# HLK_RM60_KIT_V1_1.net
KiCad netlist of a schematic drawn in Altium Designer
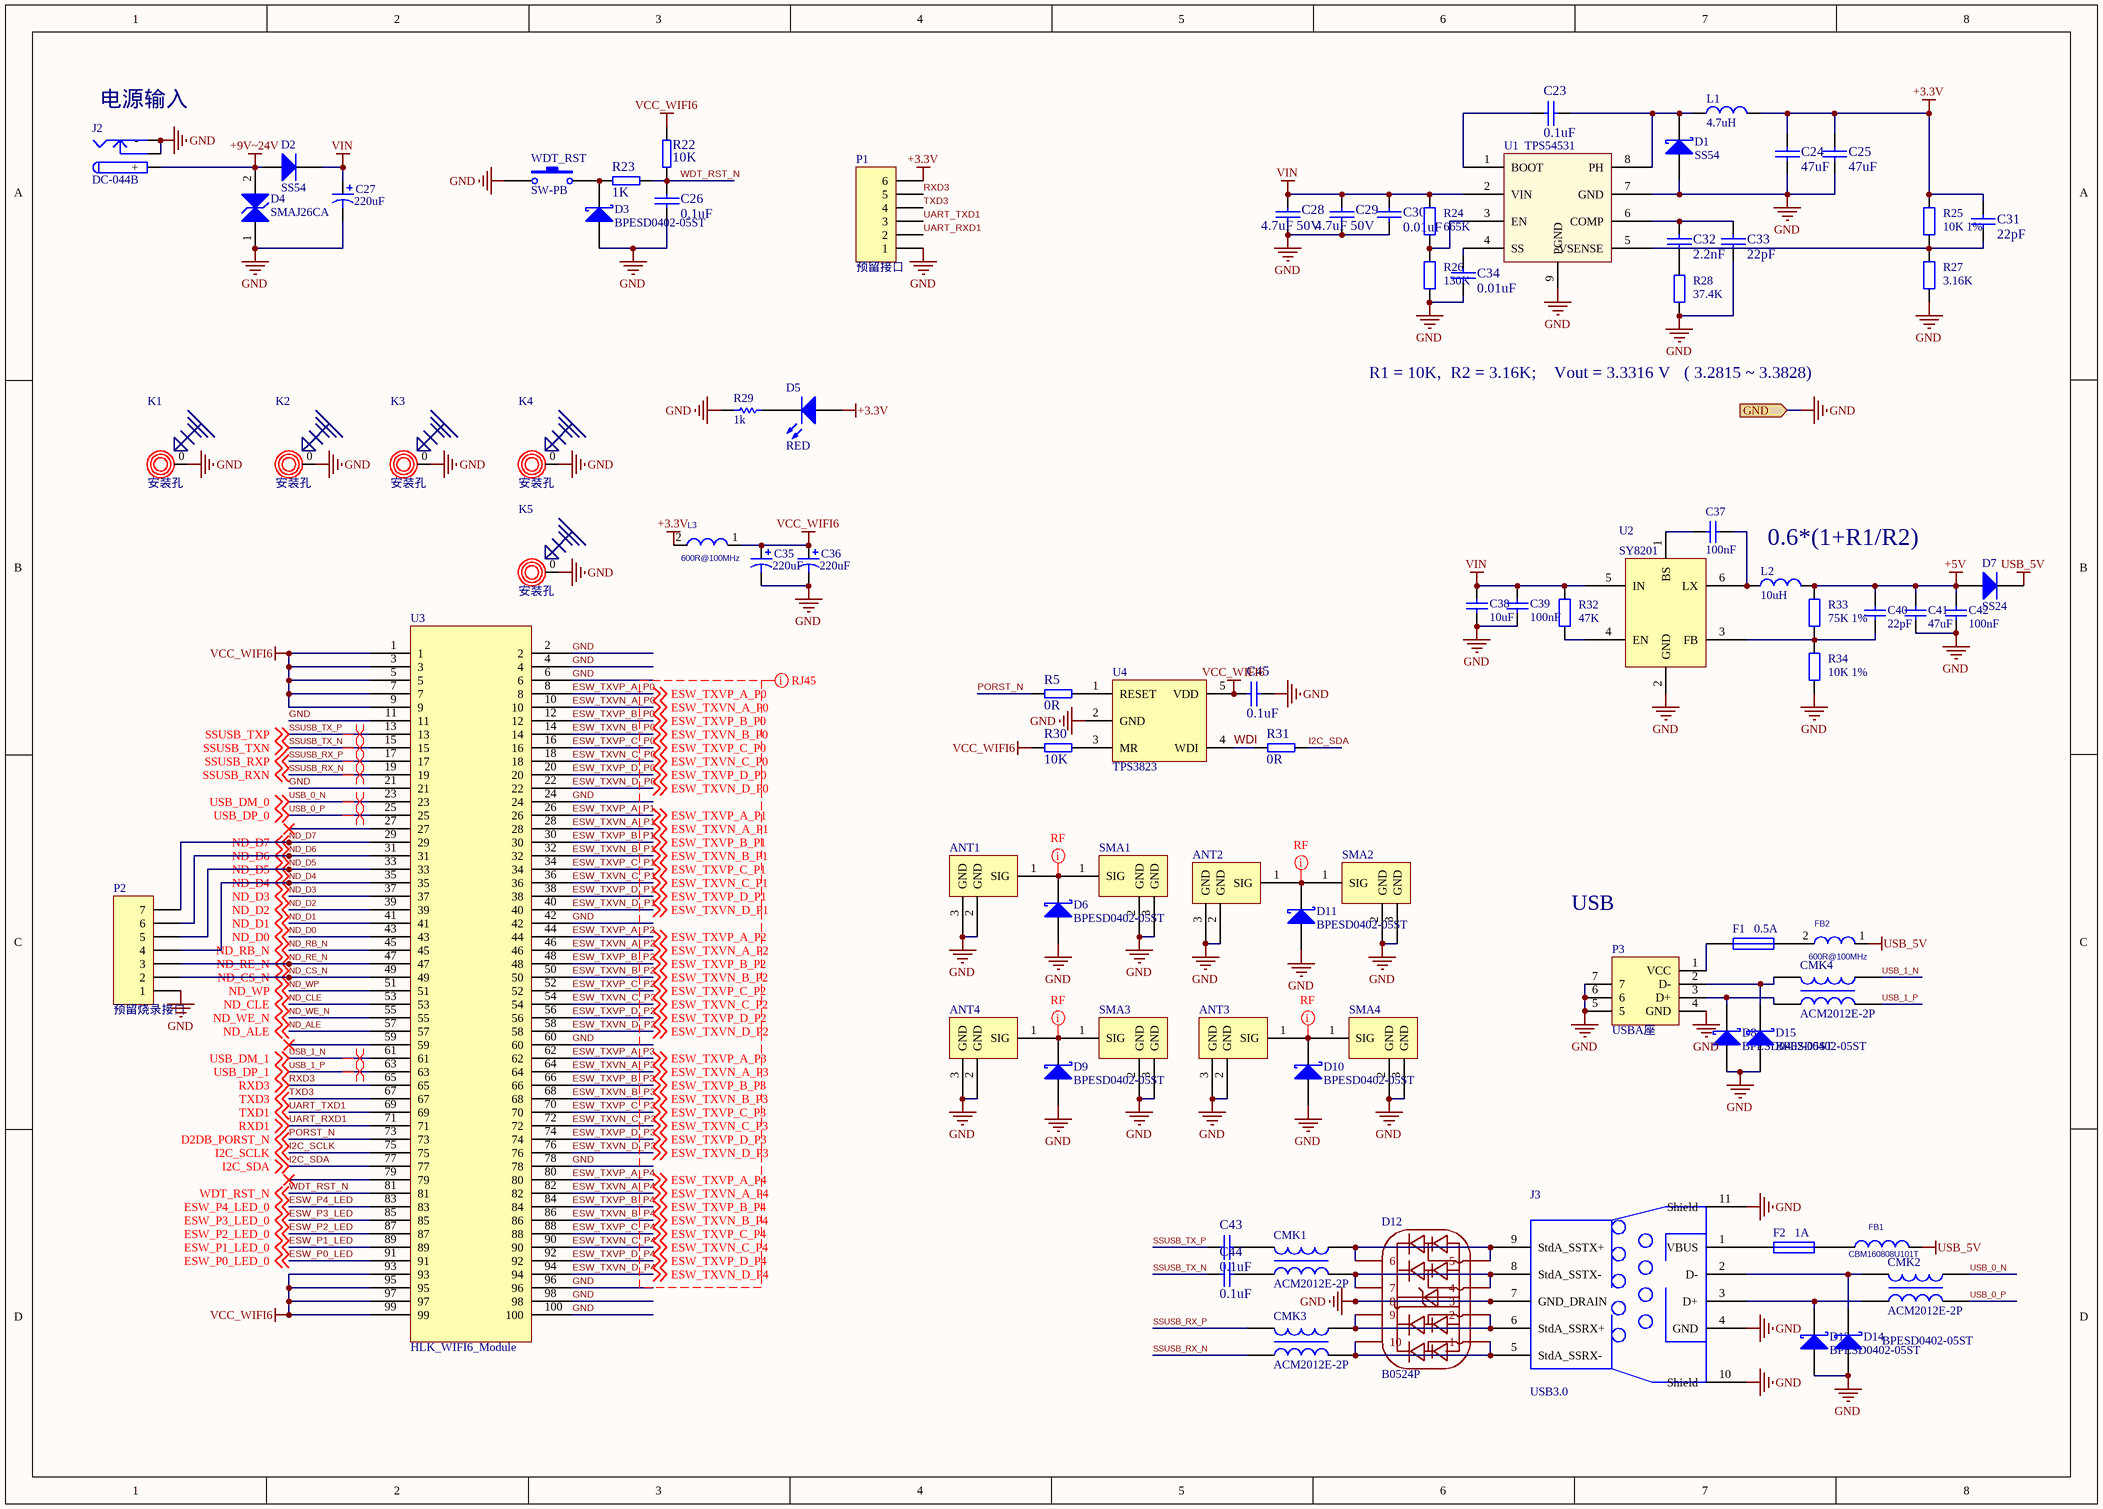
[diagram p0: HLK_RM60_KIT_V1.1.SchDoc]

(export (version "E")
  (design (tool "Eeschema 10.0.6"))
  (components
    (comp (ref "ANT1")
      (value "u.fl")
      (footprint "U.FL-R-SMT-1")
      (description "SAM天线座")
      (libsource (lib "HNCY_SCH_Lib") (part "u.fl"))
    )
    (comp (ref "ANT2")
      (value "u.fl")
      (footprint "U.FL-R-SMT-1")
      (description "SAM天线座")
      (libsource (lib "HNCY_SCH_Lib") (part "u.fl"))
    )
    (comp (ref "ANT3")
      (value "u.fl")
      (footprint "U.FL-R-SMT-1")
      (description "SAM天线座")
      (libsource (lib "HNCY_SCH_Lib") (part "u.fl"))
    )
    (comp (ref "ANT4")
      (value "u.fl")
      (footprint "U.FL-R-SMT-1")
      (description "SAM天线座")
      (libsource (lib "HNCY_SCH_Lib") (part "u.fl"))
    )
    (comp (ref "C23")
      (value "0.1uF")
      (footprint "C0402")
      (description "Capacitor")
      (libsource (lib "*") (part "CAP"))
    )
    (comp (ref "C24")
      (value "47uF")
      (footprint "CAP_1206")
      (description "Capacitor")
      (libsource (lib "*") (part "CAP"))
    )
    (comp (ref "C25")
      (value "47uF")
      (footprint "CAP_1206")
      (description "Capacitor")
      (libsource (lib "*") (part "CAP"))
    )
    (comp (ref "C26")
      (value "0.1uF")
      (footprint "C0402")
      (description "Capacitor")
      (libsource (lib "*") (part "CAP"))
    )
    (comp (ref "C27")
      (value "220uF")
      (footprint "SMD,8x10mm")
      (description "Polarized Capacitor (Radial)")
      (fields (field (name "Comment") "Cap Pol1") (field (name "PUBLISHER") "Altium Limited"))
      (libsource (lib "Miscellaneous Devices") (part "Cap Pol1"))
    )
    (comp (ref "C28")
      (value "4.7uF 50V")
      (footprint "CAP_1206")
      (description "Capacitor")
      (libsource (lib "*") (part "CAP"))
    )
    (comp (ref "C29")
      (value "4.7uF 50V")
      (footprint "CAP_1206")
      (description "Capacitor")
      (libsource (lib "*") (part "CAP"))
    )
    (comp (ref "C30")
      (value "0.01uF")
      (footprint "C0402")
      (description "Capacitor")
      (libsource (lib "*") (part "CAP"))
    )
    (comp (ref "C31")
      (value "22pF")
      (footprint "C0402")
      (description "Capacitor")
      (libsource (lib "*") (part "CAP"))
    )
    (comp (ref "C32")
      (value "2.2nF")
      (footprint "C0402")
      (description "Capacitor")
      (libsource (lib "*") (part "CAP"))
    )
    (comp (ref "C33")
      (value "22pF")
      (footprint "C0402")
      (description "Capacitor")
      (libsource (lib "*") (part "CAP"))
    )
    (comp (ref "C34")
      (value "0.01uF")
      (footprint "C0402")
      (description "Capacitor")
      (libsource (lib "*") (part "CAP"))
    )
    (comp (ref "C35")
      (value "220uF")
      (footprint "SMD,6.3x7.7mm")
      (description "Polarized Capacitor (Radial)")
      (fields (field (name "Comment") "Cap Pol1") (field (name "PUBLISHER") "Altium Limited"))
      (libsource (lib "Miscellaneous Devices") (part "Cap Pol1"))
    )
    (comp (ref "C36")
      (value "220uF")
      (footprint "SMD,6.3x7.7mm")
      (description "Polarized Capacitor (Radial)")
      (fields (field (name "Comment") "Cap Pol1") (field (name "PUBLISHER") "Altium Limited"))
      (libsource (lib "Miscellaneous Devices") (part "Cap Pol1"))
    )
    (comp (ref "C37")
      (value "100nF")
      (footprint "C0402")
      (description "Capacitor")
      (libsource (lib "LORATEMPSENSOR_V0.02") (part "Cap"))
    )
    (comp (ref "C38")
      (value "10uF")
      (footprint "CAP_0805")
      (description "Capacitor")
      (fields
        (field (name "MANUFACTURER") "Generic Components")
        (field (name "PUBLISHER") "Altium Hobart Technology Centre")
      )
      (libsource (lib "*") (part "Cap"))
    )
    (comp (ref "C39")
      (value "100nF")
      (footprint "C0402")
      (description "Capacitor")
      (libsource (lib "LORATEMPSENSOR_V0.02") (part "Cap"))
    )
    (comp (ref "C40")
      (value "22pF")
      (footprint "C0402")
      (description "Capacitor")
      (fields
        (field (name "MANUFACTURER") "Generic Components")
        (field (name "PUBLISHER") "Altium Hobart Technology Centre")
      )
      (libsource (lib "*") (part "Cap"))
    )
    (comp (ref "C41")
      (value "47uF")
      (footprint "CAP_0805")
      (description "Capacitor")
      (fields
        (field (name "MANUFACTURER") "Generic Components")
        (field (name "PUBLISHER") "Altium Hobart Technology Centre")
      )
      (libsource (lib "*") (part "Cap"))
    )
    (comp (ref "C42")
      (value "100nF")
      (footprint "C0402")
      (description "Capacitor")
      (libsource (lib "LORATEMPSENSOR_V0.02") (part "Cap"))
    )
    (comp (ref "C43")
      (value "0.1uF")
      (footprint "C0402")
      (description "Capacitor")
      (libsource (lib "*") (part "CAP"))
    )
    (comp (ref "C44")
      (value "0.1uF")
      (footprint "C0402")
      (description "Capacitor")
      (libsource (lib "*") (part "CAP"))
    )
    (comp (ref "C45")
      (value "0.1uF")
      (footprint "C0402")
      (description "Capacitor")
      (libsource (lib "*") (part "CAP"))
    )
    (comp (ref "CMK1") (value "ACM2012E-2P") (footprint "SMD_4P") (libsource (lib "*") (part "CMK1")))
    (comp (ref "CMK2") (value "ACM2012E-2P") (footprint "SMD_4P") (libsource (lib "*") (part "CMK1")))
    (comp (ref "CMK3") (value "ACM2012E-2P") (footprint "SMD_4P") (libsource (lib "*") (part "CMK1")))
    (comp (ref "CMK4") (value "ACM2012E-2P") (footprint "SMD_4P") (libsource (lib "*") (part "CMK1")))
    (comp (ref "D1")
      (value "SS54")
      (footprint "LC-SMA(DO-214AC)_S2")
      (description "Silicon AF Schottky Diode for High-Speed Switching")
      (fields (field (name "PUBLISHER") "Altium Limited"))
      (libsource (lib "Miscellaneous Devices") (part "Diode BAS70"))
    )
    (comp (ref "D2")
      (value "SS54")
      (footprint "SMC")
      (description "Default Diode")
      (fields (field (name "PUBLISHER") "Altium Limited"))
      (libsource (lib "Miscellaneous Devices") (part "Diode"))
    )
    (comp (ref "D3")
      (value "BPESD0402-05ST")
      (footprint "R0402")
      (description "Silicon AF Schottky Diode for High-Speed Switching")
      (fields (field (name "PUBLISHER") "Altium Limited"))
      (libsource (lib "Miscellaneous Devices") (part "Diode BAS70"))
    )
    (comp (ref "D4") (value "SMAJ26CA") (footprint "DO-214AC") (libsource (lib "My Schlib") (part "TVS")))
    (comp (ref "D5")
      (value "RED")
      (footprint "LED-0603")
      (description "贴片发光二极管")
      (fields (field (name "PUBLISHER") "Altium Limited"))
      (libsource (lib "LORATEMPSENSOR_V0.02") (part "LED0"))
    )
    (comp (ref "D6")
      (value "BPESD0402-05ST")
      (footprint "RES_0603")
      (description "Silicon AF Schottky Diode for High-Speed Switching")
      (fields (field (name "PUBLISHER") "Altium Limited"))
      (libsource (lib "Miscellaneous Devices") (part "Diode BAS70"))
    )
    (comp (ref "D7")
      (value "SS24")
      (footprint "LC-SMA(DO-214AC)_S2")
      (description "Default Diode")
      (fields (field (name "PUBLISHER") "Altium Limited"))
      (libsource (lib "Miscellaneous Devices") (part "Diode"))
    )
    (comp (ref "D8")
      (value "BPESD0402-05ST")
      (footprint "R0402")
      (description "Silicon AF Schottky Diode for High-Speed Switching")
      (fields (field (name "PUBLISHER") "Altium Limited"))
      (libsource (lib "Miscellaneous Devices") (part "Diode BAS70"))
    )
    (comp (ref "D9")
      (value "BPESD0402-05ST")
      (footprint "RES_0603")
      (description "Silicon AF Schottky Diode for High-Speed Switching")
      (fields (field (name "PUBLISHER") "Altium Limited"))
      (libsource (lib "Miscellaneous Devices") (part "Diode BAS70"))
    )
    (comp (ref "D10")
      (value "BPESD0402-05ST")
      (footprint "RES_0603")
      (description "Silicon AF Schottky Diode for High-Speed Switching")
      (fields (field (name "PUBLISHER") "Altium Limited"))
      (libsource (lib "Miscellaneous Devices") (part "Diode BAS70"))
    )
    (comp (ref "D11")
      (value "BPESD0402-05ST")
      (footprint "RES_0603")
      (description "Silicon AF Schottky Diode for High-Speed Switching")
      (fields (field (name "PUBLISHER") "Altium Limited"))
      (libsource (lib "Miscellaneous Devices") (part "Diode BAS70"))
    )
    (comp (ref "D12") (value "B0524P") (footprint "DFN-10") (libsource (lib "MY SCHLIB") (part "B0524P")))
    (comp (ref "D13")
      (value "BPESD0402-05ST")
      (footprint "R0402")
      (description "Silicon AF Schottky Diode for High-Speed Switching")
      (fields (field (name "PUBLISHER") "Altium Limited"))
      (libsource (lib "Miscellaneous Devices") (part "Diode BAS70"))
    )
    (comp (ref "D14")
      (value "BPESD0402-05ST")
      (footprint "R0402")
      (description "Silicon AF Schottky Diode for High-Speed Switching")
      (fields (field (name "PUBLISHER") "Altium Limited"))
      (libsource (lib "Miscellaneous Devices") (part "Diode BAS70"))
    )
    (comp (ref "D15")
      (value "BPESD0402-05ST")
      (footprint "R0402")
      (description "Silicon AF Schottky Diode for High-Speed Switching")
      (fields (field (name "PUBLISHER") "Altium Limited"))
      (libsource (lib "Miscellaneous Devices") (part "Diode BAS70"))
    )
    (comp (ref "F1")
      (value "0.5A")
      (footprint "RES_0603")
      (description "Fuse")
      (fields (field (name "PUBLISHER") "Altium Limited"))
      (libsource (lib "Miscellaneous Devices") (part "Fuse 1"))
    )
    (comp (ref "F2")
      (value "1A")
      (footprint "RES_0603")
      (description "Fuse")
      (fields (field (name "PUBLISHER") "Altium Limited"))
      (libsource (lib "Miscellaneous Devices") (part "Fuse 1"))
    )
    (comp (ref "FB1") (value "CBM160808U101T") (footprint "CAP_0603") (libsource (lib "*") (part "INDUCTOR")))
    (comp (ref "FB2") (value "600R@100MHz") (footprint "CAP_0603") (libsource (lib "*") (part "L/0402")))
    (comp (ref "J2")
      (value "DC-044B")
      (footprint "DC5.5")
      (description "Low Voltage Power Supply Connector")
      (fields (field (name "PUBLISHER") "Altium Limited"))
      (libsource (lib "封装") (part "DC-044B"))
    )
    (comp (ref "J3")
      (value "USB3.0")
      (footprint "USB3.0-9P-DIP")
      (libsource (lib "MY SCHLIB") (part "USB3.0"))
    )
    (comp (ref "K1") (value "安装孔") (footprint "Z_LSK3.5") (libsource (lib "wp_SchLib") (part "Z_LSK")))
    (comp (ref "K2") (value "安装孔") (footprint "Z_LSK3.5") (libsource (lib "wp_SchLib") (part "Z_LSK")))
    (comp (ref "K3") (value "安装孔") (footprint "Z_LSK3.5") (libsource (lib "wp_SchLib") (part "Z_LSK")))
    (comp (ref "K4") (value "安装孔") (footprint "Z_LSK3.5") (libsource (lib "wp_SchLib") (part "Z_LSK")))
    (comp (ref "K5") (value "安装孔") (footprint "Z_LSK3.5") (libsource (lib "wp_SchLib") (part "Z_LSK")))
    (comp (ref "L1") (value "4.7uH") (footprint "L10.8x10x4mm") (libsource (lib "封装") (part "LineInductors")))
    (comp (ref "L2") (value "10uH") (footprint "L4*4") (libsource (lib "封装") (part "LineInductors")))
    (comp (ref "L3") (value "600R@100MHz") (footprint "R1206") (libsource (lib "*") (part "L/0402")))
    (comp (ref "P1")
      (value "预留接口")
      (footprint "HDR1X6")
      (description "Header, 6-Pin")
      (fields (field (name "PUBLISHER") "Altium Limited"))
      (libsource (lib "Miscellaneous Connectors") (part "Header 6"))
    )
    (comp (ref "P2")
      (value "预留烧录接口")
      (footprint "HDR1X7")
      (description "Header, 7-Pin")
      (fields (field (name "PUBLISHER") "Altium Limited"))
      (libsource (lib "Miscellaneous Connectors") (part "Header 7"))
    )
    (comp (ref "P3") (value "USBA座") (footprint "USBA座侧插") (libsource (lib "MY SCHLIB") (part "USBA座")))
    (comp (ref "R5") (value "0R") (footprint "R0402") (libsource (lib "*") (part "RES2")))
    (comp (ref "R22") (value "10K") (footprint "R0402") (libsource (lib "*") (part "RES2")))
    (comp (ref "R23") (value "1K") (footprint "R0402") (libsource (lib "*") (part "RES2")))
    (comp (ref "R24")
      (value "665K")
      (footprint "R0402")
      (description "Resistor")
      (fields (field (name "PUBLISHER") "Altium Limited"))
      (libsource (lib "Miscellaneous Devices") (part "Res2"))
    )
    (comp (ref "R25")
      (value "10K 1%")
      (footprint "R0402")
      (description "Resistor")
      (fields (field (name "PUBLISHER") "Altium Limited"))
      (libsource (lib "Miscellaneous Devices") (part "Res2"))
    )
    (comp (ref "R26")
      (value "130K")
      (footprint "R0402")
      (description "Resistor")
      (fields (field (name "PUBLISHER") "Altium Limited"))
      (libsource (lib "Miscellaneous Devices") (part "Res2"))
    )
    (comp (ref "R27")
      (value "3.16K")
      (footprint "R0402")
      (description "Resistor")
      (fields (field (name "PUBLISHER") "Altium Limited"))
      (libsource (lib "Miscellaneous Devices") (part "Res2"))
    )
    (comp (ref "R28")
      (value "37.4K")
      (footprint "R0402")
      (description "Resistor")
      (fields (field (name "PUBLISHER") "Altium Limited"))
      (libsource (lib "Miscellaneous Devices") (part "Res2"))
    )
    (comp (ref "R29")
      (value "1k")
      (footprint "R0402")
      (description "Resistor")
      (fields (field (name "Comment") "1K") (field (name "PUBLISHER") "Altium Limited"))
      (libsource (lib "Miscellaneous Devices") (part "Res1"))
    )
    (comp (ref "R30") (value "10K") (footprint "R0402") (libsource (lib "*") (part "RES2")))
    (comp (ref "R31") (value "0R") (footprint "R0402") (libsource (lib "*") (part "RES2")))
    (comp (ref "R32")
      (value "47K")
      (footprint "R0402")
      (description "Resistor")
      (fields (field (name "PUBLISHER") "Altium Limited"))
      (libsource (lib "Miscellaneous Devices") (part "Res2"))
    )
    (comp (ref "R33")
      (value "75K 1%")
      (footprint "R0402")
      (description "Resistor")
      (fields (field (name "PUBLISHER") "Altium Limited"))
      (libsource (lib "Miscellaneous Devices") (part "Res2"))
    )
    (comp (ref "R34")
      (value "10K 1%")
      (footprint "R0402")
      (description "Resistor")
      (fields (field (name "PUBLISHER") "Altium Limited"))
      (libsource (lib "Miscellaneous Devices") (part "Res2"))
    )
    (comp (ref "SMA1")
      (value "u.fl")
      (footprint "RF_SMA_夹板1.6mm")
      (description "SAM天线座")
      (libsource (lib "") (part "u.fl_1"))
    )
    (comp (ref "SMA2")
      (value "u.fl")
      (footprint "RF_SMA_夹板1.6mm")
      (description "SAM天线座")
      (libsource (lib "") (part "u.fl_1"))
    )
    (comp (ref "SMA3")
      (value "u.fl")
      (footprint "RF_SMA_夹板1.6mm")
      (description "SAM天线座")
      (libsource (lib "") (part "u.fl_1"))
    )
    (comp (ref "SMA4")
      (value "u.fl")
      (footprint "RF_SMA_夹板1.6mm")
      (description "SAM天线座")
      (libsource (lib "") (part "u.fl_1"))
    )
    (comp (ref "U1")
      (value "TPS54531")
      (footprint "SOP8-MP1484")
      (libsource (lib "MY SCHLIB") (part "TPS54531"))
    )
    (comp (ref "U2") (value "SY8201") (footprint "SOT26") (libsource (lib "MY SCHLIB") (part "SY8201")))
    (comp (ref "U3")
      (value "HLK_WIFI6_Module")
      (footprint "HLK_WIFI6_Module_SOCKET")
      (libsource (lib "MY SCHLIB") (part "HLK_WIFI6_Module"))
    )
    (comp (ref "U4") (value "TPS3823") (footprint "SOT23-5") (libsource (lib "MY SCHLIB") (part "TPS3823")))
    (comp (ref "WDT_RST")
      (value "SW-PB")
      (footprint "6x6x9.85侧按")
      (description "Switch")
      (fields (field (name "PUBLISHER") "Altium Limited"))
      (libsource (lib "Miscellaneous Devices") (part "SW-PB"))
    )
  )
  (nets
    (net (code "1") (name "+3.3V") (class "Default")
      (node (ref "C24") (pin "2") (pinfunction "2_2") (pintype "passive"))
      (node (ref "C25") (pin "2") (pinfunction "2_2") (pintype "passive"))
      (node (ref "C31") (pin "2") (pinfunction "2_2") (pintype "passive"))
      (node (ref "D5") (pin "1") (pinfunction "A_1") (pintype "passive"))
      (node (ref "L1") (pin "2") (pinfunction "2_2") (pintype "passive"))
      (node (ref "L3") (pin "2") (pinfunction "2_2") (pintype "passive"))
      (node (ref "P1") (pin "6") (pinfunction "6_6") (pintype "passive"))
      (node (ref "R25") (pin "2") (pinfunction "2_2") (pintype "passive"))
    )
    (net (code "2") (name "+5V") (class "Default")
      (node (ref "C40") (pin "2") (pinfunction "2_2") (pintype "passive"))
      (node (ref "C41") (pin "2") (pinfunction "2_2") (pintype "passive"))
      (node (ref "C42") (pin "1") (pinfunction "1_1") (pintype "passive"))
      (node (ref "D7") (pin "1") (pinfunction "A_1") (pintype "passive"))
      (node (ref "L2") (pin "2") (pinfunction "2_2") (pintype "passive"))
      (node (ref "R33") (pin "2") (pinfunction "2_2") (pintype "passive"))
    )
    (net (code "3") (name "+9V~24V") (class "Default")
      (node (ref "D2") (pin "1") (pinfunction "A_1") (pintype "passive"))
      (node (ref "D4") (pin "2") (pinfunction "2_2") (pintype "passive"))
      (node (ref "J2") (pin "1") (pinfunction "+_1") (pintype "passive"))
    )
    (net (code "4") (name "/WDI") (class "Default")
      (node (ref "R31") (pin "2") (pinfunction "2_2") (pintype "passive"))
      (node (ref "U4") (pin "4") (pinfunction "WDI_4") (pintype "passive"))
    )
    (net (code "5") (name "D2DB_PORST_N") (class "Default")
      (node (ref "R5") (pin "2") (pinfunction "2_2") (pintype "passive"))
      (node (ref "U3") (pin "73") (pinfunction "73_73") (pintype "passive"))
    )
    (net (code "6") (name "ESW_P0_LED_0") (class "Default")
      (node (ref "U3") (pin "91") (pinfunction "91_91") (pintype "passive"))
    )
    (net (code "7") (name "ESW_P1_LED_0") (class "Default")
      (node (ref "U3") (pin "89") (pinfunction "89_89") (pintype "passive"))
    )
    (net (code "8") (name "ESW_P2_LED_0") (class "Default")
      (node (ref "U3") (pin "87") (pinfunction "87_87") (pintype "passive"))
    )
    (net (code "9") (name "ESW_P3_LED_0") (class "Default")
      (node (ref "U3") (pin "85") (pinfunction "85_85") (pintype "passive"))
    )
    (net (code "10") (name "ESW_P4_LED_0") (class "Default")
      (node (ref "U3") (pin "83") (pinfunction "83_83") (pintype "passive"))
    )
    (net (code "11") (name "ESW_TXVN_A_P0") (class "Default")
      (node (ref "U3") (pin "10") (pinfunction "10_10") (pintype "passive"))
    )
    (net (code "12") (name "ESW_TXVN_A_P1") (class "Default")
      (node (ref "U3") (pin "28") (pinfunction "28_28") (pintype "passive"))
    )
    (net (code "13") (name "ESW_TXVN_A_P2") (class "Default")
      (node (ref "U3") (pin "46") (pinfunction "46_46") (pintype "passive"))
    )
    (net (code "14") (name "ESW_TXVN_A_P3") (class "Default")
      (node (ref "U3") (pin "64") (pinfunction "64_64") (pintype "passive"))
    )
    (net (code "15") (name "ESW_TXVN_A_P4") (class "Default")
      (node (ref "U3") (pin "82") (pinfunction "82_82") (pintype "passive"))
    )
    (net (code "16") (name "ESW_TXVN_B_P0") (class "Default")
      (node (ref "U3") (pin "14") (pinfunction "14_14") (pintype "passive"))
    )
    (net (code "17") (name "ESW_TXVN_B_P1") (class "Default")
      (node (ref "U3") (pin "32") (pinfunction "32_32") (pintype "passive"))
    )
    (net (code "18") (name "ESW_TXVN_B_P2") (class "Default")
      (node (ref "U3") (pin "50") (pinfunction "50_50") (pintype "passive"))
    )
    (net (code "19") (name "ESW_TXVN_B_P3") (class "Default")
      (node (ref "U3") (pin "68") (pinfunction "68_68") (pintype "passive"))
    )
    (net (code "20") (name "ESW_TXVN_B_P4") (class "Default")
      (node (ref "U3") (pin "86") (pinfunction "86_86") (pintype "passive"))
    )
    (net (code "21") (name "ESW_TXVN_C_P0") (class "Default")
      (node (ref "U3") (pin "18") (pinfunction "18_18") (pintype "passive"))
    )
    (net (code "22") (name "ESW_TXVN_C_P1") (class "Default")
      (node (ref "U3") (pin "36") (pinfunction "36_36") (pintype "passive"))
    )
    (net (code "23") (name "ESW_TXVN_C_P2") (class "Default")
      (node (ref "U3") (pin "54") (pinfunction "54_54") (pintype "passive"))
    )
    (net (code "24") (name "ESW_TXVN_C_P3") (class "Default")
      (node (ref "U3") (pin "72") (pinfunction "72_72") (pintype "passive"))
    )
    (net (code "25") (name "ESW_TXVN_C_P4") (class "Default")
      (node (ref "U3") (pin "90") (pinfunction "90_90") (pintype "passive"))
    )
    (net (code "26") (name "ESW_TXVN_D_P0") (class "Default")
      (node (ref "U3") (pin "22") (pinfunction "22_22") (pintype "passive"))
    )
    (net (code "27") (name "ESW_TXVN_D_P1") (class "Default")
      (node (ref "U3") (pin "40") (pinfunction "40_40") (pintype "passive"))
    )
    (net (code "28") (name "ESW_TXVN_D_P2") (class "Default")
      (node (ref "U3") (pin "58") (pinfunction "58_58") (pintype "passive"))
    )
    (net (code "29") (name "ESW_TXVN_D_P3") (class "Default")
      (node (ref "U3") (pin "76") (pinfunction "76_76") (pintype "passive"))
    )
    (net (code "30") (name "ESW_TXVN_D_P4") (class "Default")
      (node (ref "U3") (pin "94") (pinfunction "94_94") (pintype "passive"))
    )
    (net (code "31") (name "ESW_TXVP_A_P0") (class "Default")
      (node (ref "U3") (pin "8") (pinfunction "8_8") (pintype "passive"))
    )
    (net (code "32") (name "ESW_TXVP_A_P1") (class "Default")
      (node (ref "U3") (pin "26") (pinfunction "26_26") (pintype "passive"))
    )
    (net (code "33") (name "ESW_TXVP_A_P2") (class "Default")
      (node (ref "U3") (pin "44") (pinfunction "44_44") (pintype "passive"))
    )
    (net (code "34") (name "ESW_TXVP_A_P3") (class "Default")
      (node (ref "U3") (pin "62") (pinfunction "62_62") (pintype "passive"))
    )
    (net (code "35") (name "ESW_TXVP_A_P4") (class "Default")
      (node (ref "U3") (pin "80") (pinfunction "80_80") (pintype "passive"))
    )
    (net (code "36") (name "ESW_TXVP_B_P0") (class "Default")
      (node (ref "U3") (pin "12") (pinfunction "12_12") (pintype "passive"))
    )
    (net (code "37") (name "ESW_TXVP_B_P1") (class "Default")
      (node (ref "U3") (pin "30") (pinfunction "30_30") (pintype "passive"))
    )
    (net (code "38") (name "ESW_TXVP_B_P2") (class "Default")
      (node (ref "U3") (pin "48") (pinfunction "48_48") (pintype "passive"))
    )
    (net (code "39") (name "ESW_TXVP_B_P3") (class "Default")
      (node (ref "U3") (pin "66") (pinfunction "66_66") (pintype "passive"))
    )
    (net (code "40") (name "ESW_TXVP_B_P4") (class "Default")
      (node (ref "U3") (pin "84") (pinfunction "84_84") (pintype "passive"))
    )
    (net (code "41") (name "ESW_TXVP_C_P0") (class "Default")
      (node (ref "U3") (pin "16") (pinfunction "16_16") (pintype "passive"))
    )
    (net (code "42") (name "ESW_TXVP_C_P1") (class "Default")
      (node (ref "U3") (pin "34") (pinfunction "34_34") (pintype "passive"))
    )
    (net (code "43") (name "ESW_TXVP_C_P2") (class "Default")
      (node (ref "U3") (pin "52") (pinfunction "52_52") (pintype "passive"))
    )
    (net (code "44") (name "ESW_TXVP_C_P3") (class "Default")
      (node (ref "U3") (pin "70") (pinfunction "70_70") (pintype "passive"))
    )
    (net (code "45") (name "ESW_TXVP_C_P4") (class "Default")
      (node (ref "U3") (pin "88") (pinfunction "88_88") (pintype "passive"))
    )
    (net (code "46") (name "ESW_TXVP_D_P0") (class "Default")
      (node (ref "U3") (pin "20") (pinfunction "20_20") (pintype "passive"))
    )
    (net (code "47") (name "ESW_TXVP_D_P1") (class "Default")
      (node (ref "U3") (pin "38") (pinfunction "38_38") (pintype "passive"))
    )
    (net (code "48") (name "ESW_TXVP_D_P2") (class "Default")
      (node (ref "U3") (pin "56") (pinfunction "56_56") (pintype "passive"))
    )
    (net (code "49") (name "ESW_TXVP_D_P3") (class "Default")
      (node (ref "U3") (pin "74") (pinfunction "74_74") (pintype "passive"))
    )
    (net (code "50") (name "ESW_TXVP_D_P4") (class "Default")
      (node (ref "U3") (pin "92") (pinfunction "92_92") (pintype "passive"))
    )
    (net (code "51") (name "GND") (class "Default")
      (node (ref "ANT1") (pin "2") (pinfunction "GND_2") (pintype "passive"))
      (node (ref "ANT1") (pin "3") (pinfunction "GND_3") (pintype "passive"))
      (node (ref "ANT2") (pin "2") (pinfunction "GND_2") (pintype "passive"))
      (node (ref "ANT2") (pin "3") (pinfunction "GND_3") (pintype "passive"))
      (node (ref "ANT3") (pin "2") (pinfunction "GND_2") (pintype "passive"))
      (node (ref "ANT3") (pin "3") (pinfunction "GND_3") (pintype "passive"))
      (node (ref "ANT4") (pin "2") (pinfunction "GND_2") (pintype "passive"))
      (node (ref "ANT4") (pin "3") (pinfunction "GND_3") (pintype "passive"))
      (node (ref "C24") (pin "1") (pinfunction "1_1") (pintype "passive"))
      (node (ref "C25") (pin "1") (pinfunction "1_1") (pintype "passive"))
      (node (ref "C26") (pin "1") (pinfunction "1_1") (pintype "passive"))
      (node (ref "C27") (pin "2") (pinfunction "2_2") (pintype "passive"))
      (node (ref "C28") (pin "2") (pinfunction "2_2") (pintype "passive"))
      (node (ref "C29") (pin "2") (pinfunction "2_2") (pintype "passive"))
      (node (ref "C30") (pin "1") (pinfunction "1_1") (pintype "passive"))
      (node (ref "C33") (pin "1") (pinfunction "1_1") (pintype "passive"))
      (node (ref "C34") (pin "1") (pinfunction "1_1") (pintype "passive"))
      (node (ref "C35") (pin "2") (pinfunction "2_2") (pintype "passive"))
      (node (ref "C36") (pin "2") (pinfunction "2_2") (pintype "passive"))
      (node (ref "C38") (pin "1") (pinfunction "1_1") (pintype "passive"))
      (node (ref "C39") (pin "2") (pinfunction "2_2") (pintype "passive"))
      (node (ref "C41") (pin "1") (pinfunction "1_1") (pintype "passive"))
      (node (ref "C42") (pin "2") (pinfunction "2_2") (pintype "passive"))
      (node (ref "C45") (pin "1") (pinfunction "1_1") (pintype "passive"))
      (node (ref "D1") (pin "1") (pinfunction "A_1") (pintype "passive"))
      (node (ref "D10") (pin "1") (pinfunction "A_1") (pintype "passive"))
      (node (ref "D11") (pin "1") (pinfunction "A_1") (pintype "passive"))
      (node (ref "D12") (pin "3") (pinfunction "3_3") (pintype "passive"))
      (node (ref "D12") (pin "8") (pinfunction "8_8") (pintype "passive"))
      (node (ref "D13") (pin "1") (pinfunction "A_1") (pintype "passive"))
      (node (ref "D14") (pin "1") (pinfunction "A_1") (pintype "passive"))
      (node (ref "D15") (pin "1") (pinfunction "A_1") (pintype "passive"))
      (node (ref "D3") (pin "1") (pinfunction "A_1") (pintype "passive"))
      (node (ref "D4") (pin "1") (pinfunction "1_1") (pintype "passive"))
      (node (ref "D6") (pin "1") (pinfunction "A_1") (pintype "passive"))
      (node (ref "D8") (pin "1") (pinfunction "A_1") (pintype "passive"))
      (node (ref "D9") (pin "1") (pinfunction "A_1") (pintype "passive"))
      (node (ref "J2") (pin "2") (pinfunction "-_2") (pintype "passive"))
      (node (ref "J2") (pin "3") (pinfunction "3_3") (pintype "passive"))
      (node (ref "J3") (pin "10") (pinfunction "Shield_10") (pintype "passive"))
      (node (ref "J3") (pin "11") (pinfunction "Shield_11") (pintype "passive"))
      (node (ref "J3") (pin "4") (pinfunction "GND_4") (pintype "passive"))
      (node (ref "J3") (pin "7") (pinfunction "GND_DRAIN_7") (pintype "passive"))
      (node (ref "K1") (pin "0") (pinfunction "0_0") (pintype "passive"))
      (node (ref "K2") (pin "0") (pinfunction "0_0") (pintype "passive"))
      (node (ref "K3") (pin "0") (pinfunction "0_0") (pintype "passive"))
      (node (ref "K4") (pin "0") (pinfunction "0_0") (pintype "passive"))
      (node (ref "K5") (pin "0") (pinfunction "0_0") (pintype "passive"))
      (node (ref "P1") (pin "1") (pinfunction "1_1") (pintype "passive"))
      (node (ref "P2") (pin "1") (pinfunction "1_1") (pintype "passive"))
      (node (ref "P3") (pin "4") (pinfunction "GND_4") (pintype "passive"))
      (node (ref "P3") (pin "5") (pinfunction "5_5") (pintype "passive"))
      (node (ref "P3") (pin "6") (pinfunction "6_6") (pintype "passive"))
      (node (ref "P3") (pin "7") (pinfunction "7_7") (pintype "passive"))
      (node (ref "R26") (pin "1") (pinfunction "1_1") (pintype "passive"))
      (node (ref "R27") (pin "1") (pinfunction "1_1") (pintype "passive"))
      (node (ref "R28") (pin "1") (pinfunction "1_1") (pintype "passive"))
      (node (ref "R29") (pin "2") (pinfunction "2_2") (pintype "passive"))
      (node (ref "R34") (pin "1") (pinfunction "1_1") (pintype "passive"))
      (node (ref "SMA1") (pin "2") (pinfunction "GND_2") (pintype "passive"))
      (node (ref "SMA1") (pin "3") (pinfunction "GND_3") (pintype "passive"))
      (node (ref "SMA2") (pin "2") (pinfunction "GND_2") (pintype "passive"))
      (node (ref "SMA2") (pin "3") (pinfunction "GND_3") (pintype "passive"))
      (node (ref "SMA3") (pin "2") (pinfunction "GND_2") (pintype "passive"))
      (node (ref "SMA3") (pin "3") (pinfunction "GND_3") (pintype "passive"))
      (node (ref "SMA4") (pin "2") (pinfunction "GND_2") (pintype "passive"))
      (node (ref "SMA4") (pin "3") (pinfunction "GND_3") (pintype "passive"))
      (node (ref "U1") (pin "7") (pinfunction "GND_7") (pintype "passive"))
      (node (ref "U1") (pin "9") (pinfunction "PGND_9") (pintype "passive"))
      (node (ref "U2") (pin "2") (pinfunction "GND_2") (pintype "passive"))
      (node (ref "U3") (pin "100") (pinfunction "100_100") (pintype "passive"))
      (node (ref "U3") (pin "11") (pinfunction "11_11") (pintype "passive"))
      (node (ref "U3") (pin "2") (pinfunction "2_2") (pintype "passive"))
      (node (ref "U3") (pin "21") (pinfunction "21_21") (pintype "passive"))
      (node (ref "U3") (pin "24") (pinfunction "24_24") (pintype "passive"))
      (node (ref "U3") (pin "4") (pinfunction "4_4") (pintype "passive"))
      (node (ref "U3") (pin "42") (pinfunction "42_42") (pintype "passive"))
      (node (ref "U3") (pin "6") (pinfunction "6_6") (pintype "passive"))
      (node (ref "U3") (pin "60") (pinfunction "60_60") (pintype "passive"))
      (node (ref "U3") (pin "78") (pinfunction "78_78") (pintype "passive"))
      (node (ref "U3") (pin "96") (pinfunction "96_96") (pintype "passive"))
      (node (ref "U3") (pin "98") (pinfunction "98_98") (pintype "passive"))
      (node (ref "U4") (pin "2") (pinfunction "GND_2") (pintype "passive"))
      (node (ref "WDT_RST") (pin "1") (pinfunction "1_1") (pintype "passive"))
    )
    (net (code "52") (name "I2C_SCLK") (class "Default")
      (node (ref "U3") (pin "75") (pinfunction "75_75") (pintype "passive"))
    )
    (net (code "53") (name "I2C_SDA") (class "Default")
      (node (ref "R31") (pin "1") (pinfunction "1_1") (pintype "passive"))
      (node (ref "U3") (pin "77") (pinfunction "77_77") (pintype "passive"))
    )
    (net (code "54") (name "ND_ALE") (class "Default")
      (node (ref "U3") (pin "57") (pinfunction "57_57") (pintype "passive"))
    )
    (net (code "55") (name "ND_CLE") (class "Default")
      (node (ref "U3") (pin "53") (pinfunction "53_53") (pintype "passive"))
    )
    (net (code "56") (name "ND_CS_N") (class "Default")
      (node (ref "P2") (pin "2") (pinfunction "2_2") (pintype "passive"))
      (node (ref "U3") (pin "49") (pinfunction "49_49") (pintype "passive"))
    )
    (net (code "57") (name "ND_D0") (class "Default")
      (node (ref "U3") (pin "43") (pinfunction "43_43") (pintype "passive"))
    )
    (net (code "58") (name "ND_D1") (class "Default")
      (node (ref "U3") (pin "41") (pinfunction "41_41") (pintype "passive"))
    )
    (net (code "59") (name "ND_D2") (class "Default")
      (node (ref "U3") (pin "39") (pinfunction "39_39") (pintype "passive"))
    )
    (net (code "60") (name "ND_D3") (class "Default")
      (node (ref "U3") (pin "37") (pinfunction "37_37") (pintype "passive"))
    )
    (net (code "61") (name "ND_D4") (class "Default")
      (node (ref "P2") (pin "4") (pinfunction "4_4") (pintype "passive"))
      (node (ref "U3") (pin "35") (pinfunction "35_35") (pintype "passive"))
    )
    (net (code "62") (name "ND_D5") (class "Default")
      (node (ref "P2") (pin "5") (pinfunction "5_5") (pintype "passive"))
      (node (ref "U3") (pin "33") (pinfunction "33_33") (pintype "passive"))
    )
    (net (code "63") (name "ND_D6") (class "Default")
      (node (ref "P2") (pin "6") (pinfunction "6_6") (pintype "passive"))
      (node (ref "U3") (pin "31") (pinfunction "31_31") (pintype "passive"))
    )
    (net (code "64") (name "ND_D7") (class "Default")
      (node (ref "P2") (pin "7") (pinfunction "7_7") (pintype "passive"))
      (node (ref "U3") (pin "29") (pinfunction "29_29") (pintype "passive"))
    )
    (net (code "65") (name "ND_RB_N") (class "Default")
      (node (ref "U3") (pin "45") (pinfunction "45_45") (pintype "passive"))
    )
    (net (code "66") (name "ND_RE_N") (class "Default")
      (node (ref "P2") (pin "3") (pinfunction "3_3") (pintype "passive"))
      (node (ref "U3") (pin "47") (pinfunction "47_47") (pintype "passive"))
    )
    (net (code "67") (name "ND_WE_N") (class "Default")
      (node (ref "U3") (pin "55") (pinfunction "55_55") (pintype "passive"))
    )
    (net (code "68") (name "ND_WP") (class "Default")
      (node (ref "U3") (pin "51") (pinfunction "51_51") (pintype "passive"))
    )
    (net (code "69") (name "Net-(ANT1-SIG)") (class "Default")
      (node (ref "ANT1") (pin "1") (pinfunction "SIG_1") (pintype "passive"))
      (node (ref "D6") (pin "2") (pinfunction "K_2") (pintype "passive"))
      (node (ref "SMA1") (pin "1") (pinfunction "SIG_1") (pintype "passive"))
    )
    (net (code "70") (name "Net-(ANT2-SIG)") (class "Default")
      (node (ref "ANT2") (pin "1") (pinfunction "SIG_1") (pintype "passive"))
      (node (ref "D11") (pin "2") (pinfunction "K_2") (pintype "passive"))
      (node (ref "SMA2") (pin "1") (pinfunction "SIG_1") (pintype "passive"))
    )
    (net (code "71") (name "Net-(ANT3-SIG)") (class "Default")
      (node (ref "ANT3") (pin "1") (pinfunction "SIG_1") (pintype "passive"))
      (node (ref "D10") (pin "2") (pinfunction "K_2") (pintype "passive"))
      (node (ref "SMA4") (pin "1") (pinfunction "SIG_1") (pintype "passive"))
    )
    (net (code "72") (name "Net-(ANT4-SIG)") (class "Default")
      (node (ref "ANT4") (pin "1") (pinfunction "SIG_1") (pintype "passive"))
      (node (ref "D9") (pin "2") (pinfunction "K_2") (pintype "passive"))
      (node (ref "SMA3") (pin "1") (pinfunction "SIG_1") (pintype "passive"))
    )
    (net (code "73") (name "Net-(C32-Pad1)") (class "Default")
      (node (ref "C32") (pin "1") (pinfunction "1_1") (pintype "passive"))
      (node (ref "R28") (pin "2") (pinfunction "2_2") (pintype "passive"))
    )
    (net (code "74") (name "Net-(C43-Pad1)") (class "Default")
      (node (ref "C43") (pin "1") (pinfunction "1_1") (pintype "passive"))
      (node (ref "CMK1") (pin "2") (pinfunction "2_2") (pintype "passive"))
    )
    (net (code "75") (name "Net-(C44-Pad1)") (class "Default")
      (node (ref "C44") (pin "1") (pinfunction "1_1") (pintype "passive"))
      (node (ref "CMK1") (pin "1") (pinfunction "1_1") (pintype "passive"))
    )
    (net (code "76") (name "Net-(D1-K)") (class "Default")
      (node (ref "C23") (pin "1") (pinfunction "1_1") (pintype "passive"))
      (node (ref "D1") (pin "2") (pinfunction "K_2") (pintype "passive"))
      (node (ref "L1") (pin "1") (pinfunction "1_1") (pintype "passive"))
      (node (ref "U1") (pin "8") (pinfunction "PH_8") (pintype "passive"))
    )
    (net (code "77") (name "Net-(D3-K)") (class "Default")
      (node (ref "D3") (pin "2") (pinfunction "K_2") (pintype "passive"))
      (node (ref "R23") (pin "1") (pinfunction "1_1") (pintype "passive"))
      (node (ref "WDT_RST") (pin "2") (pinfunction "2_2") (pintype "passive"))
    )
    (net (code "78") (name "Net-(D5-K)") (class "Default")
      (node (ref "D5") (pin "2") (pinfunction "K_2") (pintype "passive"))
      (node (ref "R29") (pin "1") (pinfunction "1_1") (pintype "passive"))
    )
    (net (code "79") (name "Net-(D8-K)") (class "Default")
      (node (ref "CMK4") (pin "1") (pinfunction "1_1") (pintype "passive"))
      (node (ref "D8") (pin "2") (pinfunction "K_2") (pintype "passive"))
      (node (ref "P3") (pin "3") (pinfunction "D+_3") (pintype "passive"))
    )
    (net (code "80") (name "Net-(D13-K)") (class "Default")
      (node (ref "CMK2") (pin "1") (pinfunction "1_1") (pintype "passive"))
      (node (ref "D13") (pin "2") (pinfunction "K_2") (pintype "passive"))
      (node (ref "J3") (pin "3") (pinfunction "D+_3") (pintype "passive"))
    )
    (net (code "81") (name "Net-(D14-K)") (class "Default")
      (node (ref "CMK2") (pin "2") (pinfunction "2_2") (pintype "passive"))
      (node (ref "D14") (pin "2") (pinfunction "K_2") (pintype "passive"))
      (node (ref "J3") (pin "2") (pinfunction "D-_2") (pintype "passive"))
    )
    (net (code "82") (name "Net-(D15-K)") (class "Default")
      (node (ref "CMK4") (pin "2") (pinfunction "2_2") (pintype "passive"))
      (node (ref "D15") (pin "2") (pinfunction "K_2") (pintype "passive"))
      (node (ref "P3") (pin "2") (pinfunction "D-_2") (pintype "passive"))
    )
    (net (code "83") (name "Net-(F1-Pad2)") (class "Default")
      (node (ref "F1") (pin "2") (pinfunction "2_2") (pintype "passive"))
      (node (ref "FB2") (pin "2") (pinfunction "2_2") (pintype "passive"))
    )
    (net (code "84") (name "Net-(F2-Pad2)") (class "Default")
      (node (ref "F2") (pin "2") (pinfunction "2_2") (pintype "passive"))
      (node (ref "FB1") (pin "2") (pinfunction "2_2") (pintype "passive"))
    )
    (net (code "85") (name "Net-(J3-StdA_SSRX+)") (class "Default")
      (node (ref "CMK3") (pin "3") (pinfunction "3_3") (pintype "passive"))
      (node (ref "D12") (pin "2") (pinfunction "2_2") (pintype "passive"))
      (node (ref "D12") (pin "9") (pinfunction "9_9") (pintype "passive"))
      (node (ref "J3") (pin "6") (pinfunction "StdA_SSRX+_6") (pintype "passive"))
    )
    (net (code "86") (name "Net-(J3-StdA_SSRX-)") (class "Default")
      (node (ref "CMK3") (pin "4") (pinfunction "4_4") (pintype "passive"))
      (node (ref "D12") (pin "1") (pinfunction "1_1") (pintype "passive"))
      (node (ref "D12") (pin "10") (pinfunction "10_10") (pintype "passive"))
      (node (ref "J3") (pin "5") (pinfunction "StdA_SSRX-_5") (pintype "passive"))
    )
    (net (code "87") (name "Net-(J3-StdA_SSTX+)") (class "Default")
      (node (ref "CMK1") (pin "3") (pinfunction "3_3") (pintype "passive"))
      (node (ref "D12") (pin "5") (pinfunction "5_5") (pintype "passive"))
      (node (ref "D12") (pin "6") (pinfunction "6_6") (pintype "passive"))
      (node (ref "J3") (pin "9") (pinfunction "StdA_SSTX+_9") (pintype "passive"))
    )
    (net (code "88") (name "Net-(J3-StdA_SSTX-)") (class "Default")
      (node (ref "CMK1") (pin "4") (pinfunction "4_4") (pintype "passive"))
      (node (ref "D12") (pin "4") (pinfunction "4_4") (pintype "passive"))
      (node (ref "D12") (pin "7") (pinfunction "7_7") (pintype "passive"))
      (node (ref "J3") (pin "8") (pinfunction "StdA_SSTX-_8") (pintype "passive"))
    )
    (net (code "89") (name "Net-(J3-VBUS)") (class "Default")
      (node (ref "F2") (pin "1") (pinfunction "1_1") (pintype "passive"))
      (node (ref "J3") (pin "1") (pinfunction "VBUS_1") (pintype "passive"))
    )
    (net (code "90") (name "Net-(P3-VCC)") (class "Default")
      (node (ref "F1") (pin "1") (pinfunction "1_1") (pintype "passive"))
      (node (ref "P3") (pin "1") (pinfunction "VCC_1") (pintype "passive"))
    )
    (net (code "91") (name "Net-(U1-BOOT)") (class "Default")
      (node (ref "C23") (pin "2") (pinfunction "2_2") (pintype "passive"))
      (node (ref "U1") (pin "1") (pinfunction "BOOT_1") (pintype "passive"))
    )
    (net (code "92") (name "Net-(U1-COMP)") (class "Default")
      (node (ref "C32") (pin "2") (pinfunction "2_2") (pintype "passive"))
      (node (ref "C33") (pin "2") (pinfunction "2_2") (pintype "passive"))
      (node (ref "U1") (pin "6") (pinfunction "COMP_6") (pintype "passive"))
    )
    (net (code "93") (name "Net-(U1-EN)") (class "Default")
      (node (ref "R24") (pin "1") (pinfunction "1_1") (pintype "passive"))
      (node (ref "R26") (pin "2") (pinfunction "2_2") (pintype "passive"))
      (node (ref "U1") (pin "3") (pinfunction "EN_3") (pintype "passive"))
    )
    (net (code "94") (name "Net-(U1-SS)") (class "Default")
      (node (ref "C34") (pin "2") (pinfunction "2_2") (pintype "passive"))
      (node (ref "U1") (pin "4") (pinfunction "SS_4") (pintype "passive"))
    )
    (net (code "95") (name "Net-(U1-VSENSE)") (class "Default")
      (node (ref "C31") (pin "1") (pinfunction "1_1") (pintype "passive"))
      (node (ref "R25") (pin "1") (pinfunction "1_1") (pintype "passive"))
      (node (ref "R27") (pin "2") (pinfunction "2_2") (pintype "passive"))
      (node (ref "U1") (pin "5") (pinfunction "VSENSE_5") (pintype "passive"))
    )
    (net (code "96") (name "Net-(U2-BS)") (class "Default")
      (node (ref "C37") (pin "1") (pinfunction "1_1") (pintype "passive"))
      (node (ref "U2") (pin "1") (pinfunction "BS_1") (pintype "passive"))
    )
    (net (code "97") (name "Net-(U2-EN)") (class "Default")
      (node (ref "R32") (pin "1") (pinfunction "1_1") (pintype "passive"))
      (node (ref "U2") (pin "4") (pinfunction "EN_4") (pintype "passive"))
    )
    (net (code "98") (name "Net-(U2-FB)") (class "Default")
      (node (ref "C40") (pin "1") (pinfunction "1_1") (pintype "passive"))
      (node (ref "R33") (pin "1") (pinfunction "1_1") (pintype "passive"))
      (node (ref "R34") (pin "2") (pinfunction "2_2") (pintype "passive"))
      (node (ref "U2") (pin "3") (pinfunction "FB_3") (pintype "passive"))
    )
    (net (code "99") (name "Net-(U2-LX)") (class "Default")
      (node (ref "C37") (pin "2") (pinfunction "2_2") (pintype "passive"))
      (node (ref "L2") (pin "1") (pinfunction "1_1") (pintype "passive"))
      (node (ref "U2") (pin "6") (pinfunction "LX_6") (pintype "passive"))
    )
    (net (code "100") (name "Net-(U4-MR)") (class "Default")
      (node (ref "R30") (pin "1") (pinfunction "1_1") (pintype "passive"))
      (node (ref "U4") (pin "3") (pinfunction "MR_3") (pintype "passive"))
    )
    (net (code "101") (name "Net-(U4-RESET)") (class "Default")
      (node (ref "R5") (pin "1") (pinfunction "1_1") (pintype "passive"))
      (node (ref "U4") (pin "1") (pinfunction "RESET_1") (pintype "passive"))
    )
    (net (code "102") (name "RXD1") (class "Default")
      (node (ref "P1") (pin "2") (pinfunction "2_2") (pintype "passive"))
      (node (ref "U3") (pin "71") (pinfunction "71_71") (pintype "passive"))
    )
    (net (code "103") (name "RXD3") (class "Default")
      (node (ref "P1") (pin "5") (pinfunction "5_5") (pintype "passive"))
      (node (ref "U3") (pin "65") (pinfunction "65_65") (pintype "passive"))
    )
    (net (code "104") (name "SSUSB_RXN") (class "Default")
      (node (ref "CMK3") (pin "1") (pinfunction "1_1") (pintype "passive"))
      (node (ref "U3") (pin "19") (pinfunction "19_19") (pintype "passive"))
    )
    (net (code "105") (name "SSUSB_RXP") (class "Default")
      (node (ref "CMK3") (pin "2") (pinfunction "2_2") (pintype "passive"))
      (node (ref "U3") (pin "17") (pinfunction "17_17") (pintype "passive"))
    )
    (net (code "106") (name "SSUSB_TXN") (class "Default")
      (node (ref "C44") (pin "2") (pinfunction "2_2") (pintype "passive"))
      (node (ref "U3") (pin "15") (pinfunction "15_15") (pintype "passive"))
    )
    (net (code "107") (name "SSUSB_TXP") (class "Default")
      (node (ref "C43") (pin "2") (pinfunction "2_2") (pintype "passive"))
      (node (ref "U3") (pin "13") (pinfunction "13_13") (pintype "passive"))
    )
    (net (code "108") (name "TXD1") (class "Default")
      (node (ref "P1") (pin "3") (pinfunction "3_3") (pintype "passive"))
      (node (ref "U3") (pin "69") (pinfunction "69_69") (pintype "passive"))
    )
    (net (code "109") (name "TXD3") (class "Default")
      (node (ref "P1") (pin "4") (pinfunction "4_4") (pintype "passive"))
      (node (ref "U3") (pin "67") (pinfunction "67_67") (pintype "passive"))
    )
    (net (code "110") (name "USB_5V") (class "Default")
      (node (ref "D7") (pin "2") (pinfunction "K_2") (pintype "passive"))
      (node (ref "FB1") (pin "1") (pinfunction "1_1") (pintype "passive"))
      (node (ref "FB2") (pin "1") (pinfunction "1_1") (pintype "passive"))
    )
    (net (code "111") (name "USB_DM_0") (class "Default")
      (node (ref "CMK2") (pin "3") (pinfunction "3_3") (pintype "passive"))
      (node (ref "U3") (pin "23") (pinfunction "23_23") (pintype "passive"))
    )
    (net (code "112") (name "USB_DM_1") (class "Default")
      (node (ref "CMK4") (pin "3") (pinfunction "3_3") (pintype "passive"))
      (node (ref "U3") (pin "61") (pinfunction "61_61") (pintype "passive"))
    )
    (net (code "113") (name "USB_DP_0") (class "Default")
      (node (ref "CMK2") (pin "4") (pinfunction "4_4") (pintype "passive"))
      (node (ref "U3") (pin "25") (pinfunction "25_25") (pintype "passive"))
    )
    (net (code "114") (name "USB_DP_1") (class "Default")
      (node (ref "CMK4") (pin "4") (pinfunction "4_4") (pintype "passive"))
      (node (ref "U3") (pin "63") (pinfunction "63_63") (pintype "passive"))
    )
    (net (code "115") (name "VCC_WIFI6") (class "Default")
      (node (ref "C35") (pin "1") (pinfunction "1_1") (pintype "passive"))
      (node (ref "C36") (pin "1") (pinfunction "1_1") (pintype "passive"))
      (node (ref "C45") (pin "2") (pinfunction "2_2") (pintype "passive"))
      (node (ref "L3") (pin "1") (pinfunction "1_1") (pintype "passive"))
      (node (ref "R22") (pin "1") (pinfunction "1_1") (pintype "passive"))
      (node (ref "R30") (pin "2") (pinfunction "2_2") (pintype "passive"))
      (node (ref "U3") (pin "1") (pinfunction "1_1") (pintype "passive"))
      (node (ref "U3") (pin "3") (pinfunction "3_3") (pintype "passive"))
      (node (ref "U3") (pin "5") (pinfunction "5_5") (pintype "passive"))
      (node (ref "U3") (pin "7") (pinfunction "7_7") (pintype "passive"))
      (node (ref "U3") (pin "9") (pinfunction "9_9") (pintype "passive"))
      (node (ref "U3") (pin "93") (pinfunction "93_93") (pintype "passive"))
      (node (ref "U3") (pin "95") (pinfunction "95_95") (pintype "passive"))
      (node (ref "U3") (pin "97") (pinfunction "97_97") (pintype "passive"))
      (node (ref "U3") (pin "99") (pinfunction "99_99") (pintype "passive"))
      (node (ref "U4") (pin "5") (pinfunction "VDD_5") (pintype "passive"))
    )
    (net (code "116") (name "VIN") (class "Default")
      (node (ref "C27") (pin "1") (pinfunction "1_1") (pintype "passive"))
      (node (ref "C28") (pin "1") (pinfunction "1_1") (pintype "passive"))
      (node (ref "C29") (pin "1") (pinfunction "1_1") (pintype "passive"))
      (node (ref "C30") (pin "2") (pinfunction "2_2") (pintype "passive"))
      (node (ref "C38") (pin "2") (pinfunction "2_2") (pintype "passive"))
      (node (ref "C39") (pin "1") (pinfunction "1_1") (pintype "passive"))
      (node (ref "D2") (pin "2") (pinfunction "K_2") (pintype "passive"))
      (node (ref "R24") (pin "2") (pinfunction "2_2") (pintype "passive"))
      (node (ref "R32") (pin "2") (pinfunction "2_2") (pintype "passive"))
      (node (ref "U1") (pin "2") (pinfunction "VIN_2") (pintype "passive"))
      (node (ref "U2") (pin "5") (pinfunction "IN_5") (pintype "passive"))
    )
    (net (code "117") (name "WDT_RST_N") (class "Default")
      (node (ref "C26") (pin "2") (pinfunction "2_2") (pintype "passive"))
      (node (ref "R22") (pin "2") (pinfunction "2_2") (pintype "passive"))
      (node (ref "R23") (pin "2") (pinfunction "2_2") (pintype "passive"))
      (node (ref "U3") (pin "81") (pinfunction "81_81") (pintype "passive"))
    )
    (net (code "118") (name "unconnected-(U3-Pad27)") (class "Default")
      (node (ref "U3") (pin "27") (pinfunction "27_27") (pintype "passive+no_connect"))
    )
    (net (code "119") (name "unconnected-(U3-Pad59)") (class "Default")
      (node (ref "U3") (pin "59") (pinfunction "59_59") (pintype "passive+no_connect"))
    )
    (net (code "120") (name "unconnected-(U3-Pad79)") (class "Default")
      (node (ref "U3") (pin "79") (pinfunction "79_79") (pintype "passive+no_connect"))
    )
  )
)
